# RJ45x5.net
KiCad netlist of a schematic drawn in EAGLE
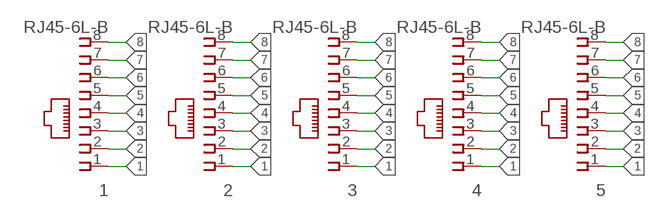
[diagram p0: schematic, sheet 1]

(export (version "E")
  (design (tool "Eeschema 10.0.6"))
  (components
    (comp (ref "1")
      (value "RJ45-6L-B")
      (footprint "eagle-import:RJ45-NO-SHIELD")
      (libsource (lib "eagle-import") (part "RJ45-6L-B"))
    )
    (comp (ref "2")
      (value "RJ45-6L-B")
      (footprint "eagle-import:RJ45-NO-SHIELD")
      (libsource (lib "eagle-import") (part "RJ45-6L-B"))
    )
    (comp (ref "3")
      (value "RJ45-6L-B")
      (footprint "eagle-import:RJ45-NO-SHIELD")
      (libsource (lib "eagle-import") (part "RJ45-6L-B"))
    )
    (comp (ref "4")
      (value "RJ45-6L-B")
      (footprint "eagle-import:RJ45-NO-SHIELD")
      (libsource (lib "eagle-import") (part "RJ45-6L-B"))
    )
    (comp (ref "5")
      (value "RJ45-6L-B")
      (footprint "eagle-import:RJ45-NO-SHIELD")
      (libsource (lib "eagle-import") (part "RJ45-6L-B"))
    )
  )
  (nets
    (net (code "1") (name "1") (class "Default")
      (node (ref "1") (pin "1") (pinfunction "1_1") (pintype "passive"))
      (node (ref "2") (pin "1") (pinfunction "1_1") (pintype "passive"))
      (node (ref "3") (pin "1") (pinfunction "1_1") (pintype "passive"))
      (node (ref "4") (pin "1") (pinfunction "1_1") (pintype "passive"))
      (node (ref "5") (pin "1") (pinfunction "1_1") (pintype "passive"))
    )
    (net (code "2") (name "2") (class "Default")
      (node (ref "1") (pin "2") (pinfunction "2_2") (pintype "passive"))
      (node (ref "2") (pin "2") (pinfunction "2_2") (pintype "passive"))
      (node (ref "3") (pin "2") (pinfunction "2_2") (pintype "passive"))
      (node (ref "4") (pin "2") (pinfunction "2_2") (pintype "passive"))
      (node (ref "5") (pin "2") (pinfunction "2_2") (pintype "passive"))
    )
    (net (code "3") (name "3") (class "Default")
      (node (ref "1") (pin "3") (pinfunction "3_3") (pintype "passive"))
      (node (ref "2") (pin "3") (pinfunction "3_3") (pintype "passive"))
      (node (ref "3") (pin "3") (pinfunction "3_3") (pintype "passive"))
      (node (ref "4") (pin "3") (pinfunction "3_3") (pintype "passive"))
      (node (ref "5") (pin "3") (pinfunction "3_3") (pintype "passive"))
    )
    (net (code "4") (name "4") (class "Default")
      (node (ref "1") (pin "4") (pinfunction "4_4") (pintype "passive"))
      (node (ref "2") (pin "4") (pinfunction "4_4") (pintype "passive"))
      (node (ref "3") (pin "4") (pinfunction "4_4") (pintype "passive"))
      (node (ref "4") (pin "4") (pinfunction "4_4") (pintype "passive"))
      (node (ref "5") (pin "4") (pinfunction "4_4") (pintype "passive"))
    )
    (net (code "5") (name "5") (class "Default")
      (node (ref "1") (pin "5") (pinfunction "5_5") (pintype "passive"))
      (node (ref "2") (pin "5") (pinfunction "5_5") (pintype "passive"))
      (node (ref "3") (pin "5") (pinfunction "5_5") (pintype "passive"))
      (node (ref "4") (pin "5") (pinfunction "5_5") (pintype "passive"))
      (node (ref "5") (pin "5") (pinfunction "5_5") (pintype "passive"))
    )
    (net (code "6") (name "6") (class "Default")
      (node (ref "1") (pin "6") (pinfunction "6_6") (pintype "passive"))
      (node (ref "2") (pin "6") (pinfunction "6_6") (pintype "passive"))
      (node (ref "3") (pin "6") (pinfunction "6_6") (pintype "passive"))
      (node (ref "4") (pin "6") (pinfunction "6_6") (pintype "passive"))
      (node (ref "5") (pin "6") (pinfunction "6_6") (pintype "passive"))
    )
    (net (code "7") (name "7") (class "Default")
      (node (ref "1") (pin "7") (pinfunction "7_7") (pintype "passive"))
      (node (ref "2") (pin "7") (pinfunction "7_7") (pintype "passive"))
      (node (ref "3") (pin "7") (pinfunction "7_7") (pintype "passive"))
      (node (ref "4") (pin "7") (pinfunction "7_7") (pintype "passive"))
      (node (ref "5") (pin "7") (pinfunction "7_7") (pintype "passive"))
    )
    (net (code "8") (name "8") (class "Default")
      (node (ref "1") (pin "8") (pinfunction "8_8") (pintype "passive"))
      (node (ref "2") (pin "8") (pinfunction "8_8") (pintype "passive"))
      (node (ref "3") (pin "8") (pinfunction "8_8") (pintype "passive"))
      (node (ref "4") (pin "8") (pinfunction "8_8") (pintype "passive"))
      (node (ref "5") (pin "8") (pinfunction "8_8") (pintype "passive"))
    )
  )
)
